# headstage.net
KiCad netlist of a schematic drawn in EAGLE
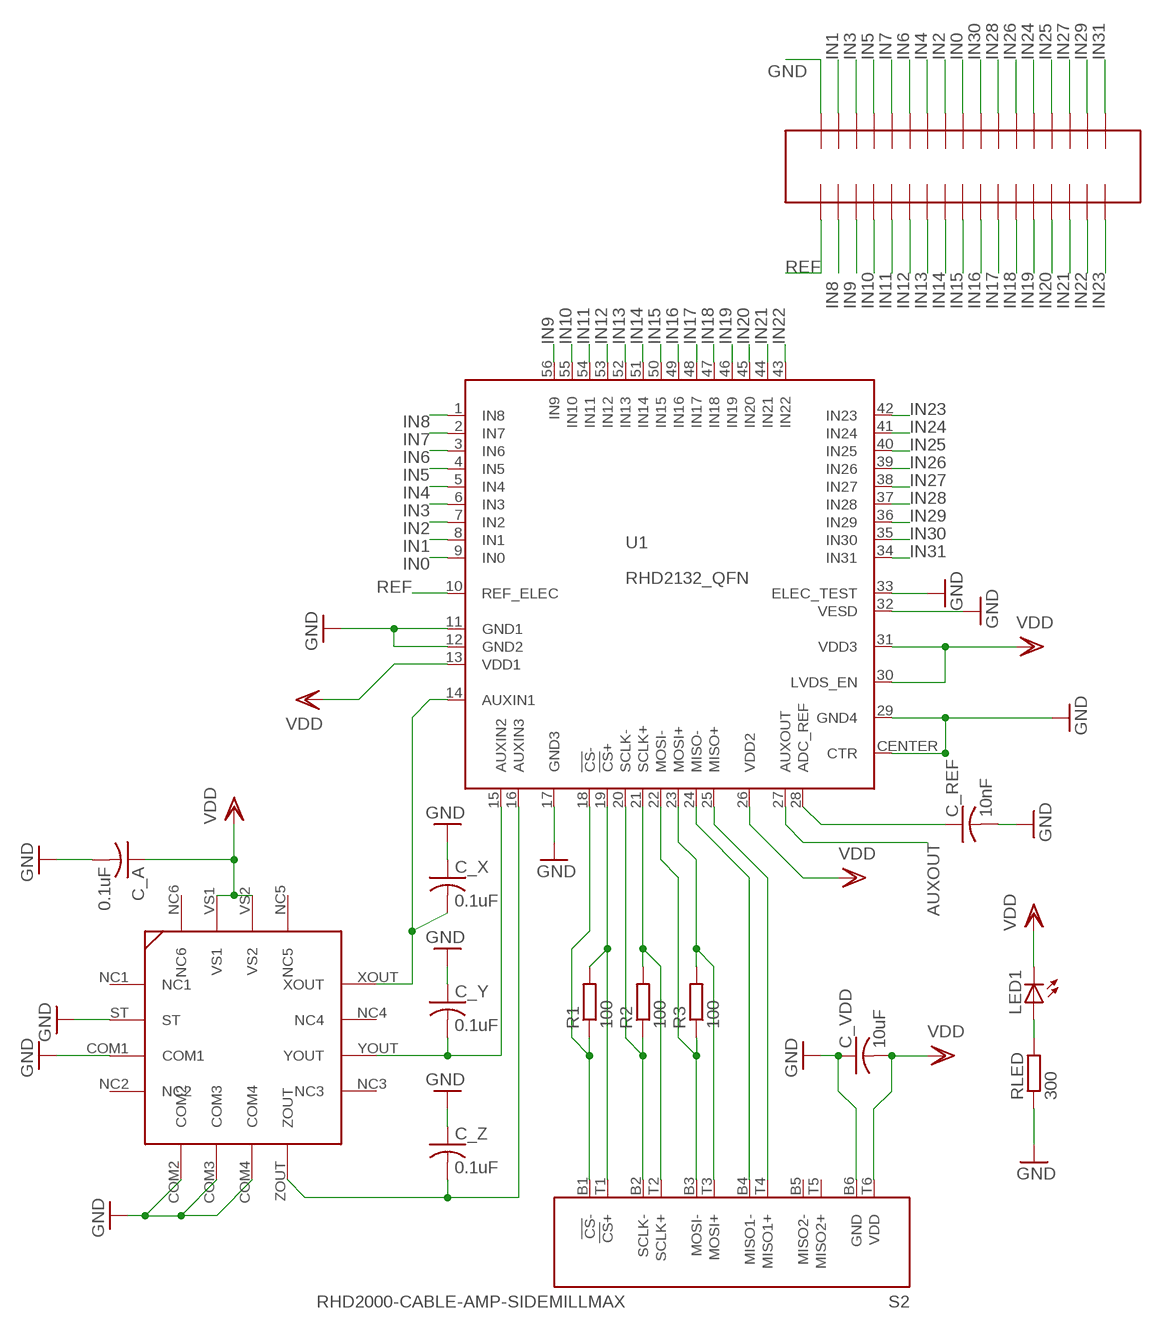
[diagram p0: schematic, sheet 1]

(export (version "E")
  (design (tool "Eeschema 10.0.6"))
  (components
    (comp (ref "C_A")
      (value "0.1uF")
      (footprint "eagle-import:C0402K")
      (libsource (lib "eagle-import") (part "resistor_C-USC0402K"))
    )
    (comp (ref "C_REF")
      (value "10nF")
      (footprint "eagle-import:C0402K")
      (libsource (lib "eagle-import") (part "resistor_C-USC0402K"))
    )
    (comp (ref "C_VDD")
      (value "10uF")
      (footprint "eagle-import:C0805")
      (libsource (lib "eagle-import") (part "C-USC0805"))
    )
    (comp (ref "C_X")
      (value "0.1uF")
      (footprint "eagle-import:C0402K")
      (libsource (lib "eagle-import") (part "resistor_C-USC0402K"))
    )
    (comp (ref "C_Y")
      (value "0.1uF")
      (footprint "eagle-import:C0402K")
      (libsource (lib "eagle-import") (part "resistor_C-USC0402K"))
    )
    (comp (ref "C_Z")
      (value "0.1uF")
      (footprint "eagle-import:C0402K")
      (libsource (lib "eagle-import") (part "resistor_C-USC0402K"))
    )
    (comp (ref "LED1")
      (value "LEDCHIPLED_0805")
      (footprint "eagle-import:CHIPLED_0805")
      (libsource (lib "eagle-import") (part "LEDCHIPLED_0805"))
    )
    (comp (ref "R1")
      (value "100")
      (footprint "eagle-import:R0402")
      (libsource (lib "eagle-import") (part "R-EU_R0402"))
    )
    (comp (ref "R2")
      (value "100")
      (footprint "eagle-import:R0402")
      (libsource (lib "eagle-import") (part "R-EU_R0402"))
    )
    (comp (ref "R3")
      (value "100")
      (footprint "eagle-import:R0402")
      (libsource (lib "eagle-import") (part "R-EU_R0402"))
    )
    (comp (ref "RLED")
      (value "300")
      (footprint "eagle-import:R0402")
      (libsource (lib "eagle-import") (part "R-EU_R0402"))
    )
    (comp (ref "S2")
      (value "RHD2000-CABLE-AMP-SIDEMILLMAX")
      (footprint "eagle-import:MILLMAX-12PIN")
      (libsource (lib "eagle-import") (part "RHD2000-CABLE-AMP-SIDEMILLMAX"))
    )
    (comp (ref "U$1")
      (value "ADXL335")
      (footprint "eagle-import:ADXL335")
      (libsource (lib "eagle-import") (part "ADXL335"))
    )
    (comp (ref "U$2")
      (value "FTSH-117BOARD-END")
      (footprint "eagle-import:FTSH-117-END")
      (libsource (lib "eagle-import") (part "FTSH-117BOARD-END"))
    )
    (comp (ref "U1")
      (value "RHD2132_QFN")
      (footprint "eagle-import:QFN56_8_X_8_LARGE")
      (libsource (lib "eagle-import") (part "RHD2132_QFN"))
    )
  )
  (nets
    (net (code "1") (name "/AUXOUT") (class "Default")
      (node (ref "U1") (pin "27") (pinfunction "AUXOUT_27") (pintype "tri_state"))
    )
    (net (code "2") (name "/IN0") (class "Default")
      (node (ref "U$2") (pin "P$26") (pinfunction "P$26_P$26") (pintype "bidirectional"))
      (node (ref "U1") (pin "9") (pinfunction "IN0_9") (pintype "input"))
    )
    (net (code "3") (name "/IN1") (class "Default")
      (node (ref "U$2") (pin "P$33") (pinfunction "P$33_P$33") (pintype "bidirectional"))
      (node (ref "U1") (pin "8") (pinfunction "IN1_8") (pintype "input"))
    )
    (net (code "4") (name "/IN2") (class "Default")
      (node (ref "U$2") (pin "P$27") (pinfunction "P$27_P$27") (pintype "bidirectional"))
      (node (ref "U1") (pin "7") (pinfunction "IN2_7") (pintype "input"))
    )
    (net (code "5") (name "/IN3") (class "Default")
      (node (ref "U$2") (pin "P$32") (pinfunction "P$32_P$32") (pintype "bidirectional"))
      (node (ref "U1") (pin "6") (pinfunction "IN3_6") (pintype "input"))
    )
    (net (code "6") (name "/IN4") (class "Default")
      (node (ref "U$2") (pin "P$28") (pinfunction "P$28_P$28") (pintype "bidirectional"))
      (node (ref "U1") (pin "5") (pinfunction "IN4_5") (pintype "input"))
    )
    (net (code "7") (name "/IN5") (class "Default")
      (node (ref "U$2") (pin "P$31") (pinfunction "P$31_P$31") (pintype "bidirectional"))
      (node (ref "U1") (pin "4") (pinfunction "IN5_4") (pintype "input"))
    )
    (net (code "8") (name "/IN6") (class "Default")
      (node (ref "U$2") (pin "P$29") (pinfunction "P$29_P$29") (pintype "bidirectional"))
      (node (ref "U1") (pin "3") (pinfunction "IN6_3") (pintype "input"))
    )
    (net (code "9") (name "/IN7") (class "Default")
      (node (ref "U$2") (pin "P$30") (pinfunction "P$30_P$30") (pintype "bidirectional"))
      (node (ref "U1") (pin "2") (pinfunction "IN7_2") (pintype "input"))
    )
    (net (code "10") (name "/IN8") (class "Default")
      (node (ref "U$2") (pin "P$2") (pinfunction "P$2_P$2") (pintype "bidirectional"))
      (node (ref "U1") (pin "1") (pinfunction "IN8_1") (pintype "input"))
    )
    (net (code "11") (name "/IN9") (class "Default")
      (node (ref "U$2") (pin "P$3") (pinfunction "P$3_P$3") (pintype "bidirectional"))
      (node (ref "U1") (pin "56") (pinfunction "IN9_56") (pintype "input"))
    )
    (net (code "12") (name "/IN10") (class "Default")
      (node (ref "U$2") (pin "P$4") (pinfunction "P$4_P$4") (pintype "bidirectional"))
      (node (ref "U1") (pin "55") (pinfunction "IN10_55") (pintype "input"))
    )
    (net (code "13") (name "/IN11") (class "Default")
      (node (ref "U$2") (pin "P$5") (pinfunction "P$5_P$5") (pintype "bidirectional"))
      (node (ref "U1") (pin "54") (pinfunction "IN11_54") (pintype "input"))
    )
    (net (code "14") (name "/IN12") (class "Default")
      (node (ref "U$2") (pin "P$6") (pinfunction "P$6_P$6") (pintype "bidirectional"))
      (node (ref "U1") (pin "53") (pinfunction "IN12_53") (pintype "input"))
    )
    (net (code "15") (name "/IN13") (class "Default")
      (node (ref "U$2") (pin "P$7") (pinfunction "P$7_P$7") (pintype "bidirectional"))
      (node (ref "U1") (pin "52") (pinfunction "IN13_52") (pintype "input"))
    )
    (net (code "16") (name "/IN14") (class "Default")
      (node (ref "U$2") (pin "P$8") (pinfunction "P$8_P$8") (pintype "bidirectional"))
      (node (ref "U1") (pin "51") (pinfunction "IN14_51") (pintype "input"))
    )
    (net (code "17") (name "/IN15") (class "Default")
      (node (ref "U$2") (pin "P$9") (pinfunction "P$9_P$9") (pintype "bidirectional"))
      (node (ref "U1") (pin "50") (pinfunction "IN15_50") (pintype "input"))
    )
    (net (code "18") (name "/IN16") (class "Default")
      (node (ref "U$2") (pin "P$10") (pinfunction "P$10_P$10") (pintype "bidirectional"))
      (node (ref "U1") (pin "49") (pinfunction "IN16_49") (pintype "input"))
    )
    (net (code "19") (name "/IN17") (class "Default")
      (node (ref "U$2") (pin "P$11") (pinfunction "P$11_P$11") (pintype "bidirectional"))
      (node (ref "U1") (pin "48") (pinfunction "IN17_48") (pintype "input"))
    )
    (net (code "20") (name "/IN18") (class "Default")
      (node (ref "U$2") (pin "P$12") (pinfunction "P$12_P$12") (pintype "bidirectional"))
      (node (ref "U1") (pin "47") (pinfunction "IN18_47") (pintype "input"))
    )
    (net (code "21") (name "/IN19") (class "Default")
      (node (ref "U$2") (pin "P$13") (pinfunction "P$13_P$13") (pintype "bidirectional"))
      (node (ref "U1") (pin "46") (pinfunction "IN19_46") (pintype "input"))
    )
    (net (code "22") (name "/IN20") (class "Default")
      (node (ref "U$2") (pin "P$14") (pinfunction "P$14_P$14") (pintype "bidirectional"))
      (node (ref "U1") (pin "45") (pinfunction "IN20_45") (pintype "input"))
    )
    (net (code "23") (name "/IN21") (class "Default")
      (node (ref "U$2") (pin "P$15") (pinfunction "P$15_P$15") (pintype "bidirectional"))
      (node (ref "U1") (pin "44") (pinfunction "IN21_44") (pintype "input"))
    )
    (net (code "24") (name "/IN22") (class "Default")
      (node (ref "U$2") (pin "P$16") (pinfunction "P$16_P$16") (pintype "bidirectional"))
      (node (ref "U1") (pin "43") (pinfunction "IN22_43") (pintype "input"))
    )
    (net (code "25") (name "/IN23") (class "Default")
      (node (ref "U$2") (pin "P$17") (pinfunction "P$17_P$17") (pintype "bidirectional"))
      (node (ref "U1") (pin "42") (pinfunction "IN23_42") (pintype "input"))
    )
    (net (code "26") (name "/IN24") (class "Default")
      (node (ref "U$2") (pin "P$22") (pinfunction "P$22_P$22") (pintype "bidirectional"))
      (node (ref "U1") (pin "41") (pinfunction "IN24_41") (pintype "input"))
    )
    (net (code "27") (name "/IN25") (class "Default")
      (node (ref "U$2") (pin "P$21") (pinfunction "P$21_P$21") (pintype "bidirectional"))
      (node (ref "U1") (pin "40") (pinfunction "IN25_40") (pintype "input"))
    )
    (net (code "28") (name "/IN26") (class "Default")
      (node (ref "U$2") (pin "P$23") (pinfunction "P$23_P$23") (pintype "bidirectional"))
      (node (ref "U1") (pin "39") (pinfunction "IN26_39") (pintype "input"))
    )
    (net (code "29") (name "/IN27") (class "Default")
      (node (ref "U$2") (pin "P$20") (pinfunction "P$20_P$20") (pintype "bidirectional"))
      (node (ref "U1") (pin "38") (pinfunction "IN27_38") (pintype "input"))
    )
    (net (code "30") (name "/IN28") (class "Default")
      (node (ref "U$2") (pin "P$24") (pinfunction "P$24_P$24") (pintype "bidirectional"))
      (node (ref "U1") (pin "37") (pinfunction "IN28_37") (pintype "input"))
    )
    (net (code "31") (name "/IN29") (class "Default")
      (node (ref "U$2") (pin "P$19") (pinfunction "P$19_P$19") (pintype "bidirectional"))
      (node (ref "U1") (pin "36") (pinfunction "IN29_36") (pintype "input"))
    )
    (net (code "32") (name "/IN30") (class "Default")
      (node (ref "U$2") (pin "P$25") (pinfunction "P$25_P$25") (pintype "bidirectional"))
      (node (ref "U1") (pin "35") (pinfunction "IN30_35") (pintype "input"))
    )
    (net (code "33") (name "/IN31") (class "Default")
      (node (ref "U$2") (pin "P$18") (pinfunction "P$18_P$18") (pintype "bidirectional"))
      (node (ref "U1") (pin "34") (pinfunction "IN31_34") (pintype "input"))
    )
    (net (code "34") (name "/REF") (class "Default")
      (node (ref "U$2") (pin "P$1") (pinfunction "P$1_P$1") (pintype "bidirectional"))
      (node (ref "U1") (pin "10") (pinfunction "REF_ELEC_10") (pintype "input"))
    )
    (net (code "35") (name "GND") (class "Default")
      (node (ref "C_A") (pin "2") (pinfunction "2_2") (pintype "passive"))
      (node (ref "C_REF") (pin "2") (pinfunction "2_2") (pintype "passive"))
      (node (ref "C_VDD") (pin "1") (pinfunction "1_1") (pintype "passive"))
      (node (ref "C_X") (pin "1") (pinfunction "1_1") (pintype "passive"))
      (node (ref "C_Y") (pin "1") (pinfunction "1_1") (pintype "passive"))
      (node (ref "C_Z") (pin "1") (pinfunction "1_1") (pintype "passive"))
      (node (ref "RLED") (pin "1") (pinfunction "1_1") (pintype "passive"))
      (node (ref "S2") (pin "B6") (pinfunction "GND_B6") (pintype "power_in"))
      (node (ref "U$1") (pin "COM1") (pinfunction "COM1_COM1") (pintype "bidirectional"))
      (node (ref "U$1") (pin "COM2") (pinfunction "COM2_COM2") (pintype "bidirectional"))
      (node (ref "U$1") (pin "COM3") (pinfunction "COM3_COM3") (pintype "bidirectional"))
      (node (ref "U$1") (pin "COM4") (pinfunction "COM4_COM4") (pintype "bidirectional"))
      (node (ref "U$1") (pin "ST") (pinfunction "ST_ST") (pintype "bidirectional"))
      (node (ref "U$2") (pin "P$34") (pinfunction "P$34_P$34") (pintype "bidirectional"))
      (node (ref "U1") (pin "11") (pinfunction "GND1_11") (pintype "power_in"))
      (node (ref "U1") (pin "12") (pinfunction "GND2_12") (pintype "power_in"))
      (node (ref "U1") (pin "17") (pinfunction "GND3_17") (pintype "power_in"))
      (node (ref "U1") (pin "29") (pinfunction "GND4_29") (pintype "power_in"))
      (node (ref "U1") (pin "32") (pinfunction "VESD_32") (pintype "power_in"))
      (node (ref "U1") (pin "33") (pinfunction "ELEC_TEST_33") (pintype "input"))
      (node (ref "U1") (pin "CENTER") (pinfunction "CTR_CENTER") (pintype "power_in"))
    )
    (net (code "36") (name "Net-(LED1-PadA)") (class "Default")
      (node (ref "LED1") (pin "A") (pinfunction "A_A") (pintype "passive"))
      (node (ref "RLED") (pin "2") (pinfunction "2_2") (pintype "passive"))
    )
    (net (code "37") (name "Net-(S2-MISO1+)") (class "Default")
      (node (ref "S2") (pin "T4") (pinfunction "MISO1+_T4") (pintype "bidirectional"))
      (node (ref "U1") (pin "25") (pinfunction "MISO+_25") (pintype "output"))
    )
    (net (code "38") (name "Net-(S2-MISO1-)") (class "Default")
      (node (ref "S2") (pin "B4") (pinfunction "MISO1-_B4") (pintype "bidirectional"))
      (node (ref "U1") (pin "24") (pinfunction "MISO-_24") (pintype "output"))
    )
    (net (code "39") (name "Net-(S2-MOSI+)") (class "Default")
      (node (ref "R3") (pin "2") (pinfunction "2_2") (pintype "passive"))
      (node (ref "S2") (pin "T3") (pinfunction "MOSI+_T3") (pintype "bidirectional"))
      (node (ref "U1") (pin "23") (pinfunction "MOSI+_23") (pintype "input"))
    )
    (net (code "40") (name "Net-(S2-MOSI-)") (class "Default")
      (node (ref "R3") (pin "1") (pinfunction "1_1") (pintype "passive"))
      (node (ref "S2") (pin "B3") (pinfunction "MOSI-_B3") (pintype "bidirectional"))
      (node (ref "U1") (pin "22") (pinfunction "MOSI-_22") (pintype "input"))
    )
    (net (code "41") (name "Net-(S2-SCLK+)") (class "Default")
      (node (ref "R2") (pin "2") (pinfunction "2_2") (pintype "passive"))
      (node (ref "S2") (pin "T2") (pinfunction "SCLK+_T2") (pintype "bidirectional"))
      (node (ref "U1") (pin "21") (pinfunction "SCLK+_21") (pintype "input"))
    )
    (net (code "42") (name "Net-(S2-SCLK-)") (class "Default")
      (node (ref "R2") (pin "1") (pinfunction "1_1") (pintype "passive"))
      (node (ref "S2") (pin "B2") (pinfunction "SCLK-_B2") (pintype "bidirectional"))
      (node (ref "U1") (pin "20") (pinfunction "SCLK-_20") (pintype "input"))
    )
    (net (code "43") (name "Net-(S2-~{CS}+)") (class "Default")
      (node (ref "R1") (pin "2") (pinfunction "2_2") (pintype "passive"))
      (node (ref "S2") (pin "T1") (pinfunction "~{CS}+_T1") (pintype "bidirectional"))
      (node (ref "U1") (pin "19") (pinfunction "~{CS}+_19") (pintype "input"))
    )
    (net (code "44") (name "Net-(S2-~{CS}-)") (class "Default")
      (node (ref "R1") (pin "1") (pinfunction "1_1") (pintype "passive"))
      (node (ref "S2") (pin "B1") (pinfunction "~{CS}-_B1") (pintype "bidirectional"))
      (node (ref "U1") (pin "18") (pinfunction "~{CS}-_18") (pintype "input"))
    )
    (net (code "45") (name "Net-(U1-ADC_REF)") (class "Default")
      (node (ref "C_REF") (pin "1") (pinfunction "1_1") (pintype "passive"))
      (node (ref "U1") (pin "28") (pinfunction "ADC_REF_28") (pintype "passive"))
    )
    (net (code "46") (name "Net-(U1-AUXIN1)") (class "Default")
      (node (ref "C_X") (pin "2") (pinfunction "2_2") (pintype "passive"))
      (node (ref "U$1") (pin "XOUT") (pinfunction "XOUT_XOUT") (pintype "bidirectional"))
      (node (ref "U1") (pin "14") (pinfunction "AUXIN1_14") (pintype "input"))
    )
    (net (code "47") (name "Net-(U1-AUXIN2)") (class "Default")
      (node (ref "C_Y") (pin "2") (pinfunction "2_2") (pintype "passive"))
      (node (ref "U$1") (pin "YOUT") (pinfunction "YOUT_YOUT") (pintype "bidirectional"))
      (node (ref "U1") (pin "15") (pinfunction "AUXIN2_15") (pintype "input"))
    )
    (net (code "48") (name "Net-(U1-AUXIN3)") (class "Default")
      (node (ref "C_Z") (pin "2") (pinfunction "2_2") (pintype "passive"))
      (node (ref "U$1") (pin "ZOUT") (pinfunction "ZOUT_ZOUT") (pintype "bidirectional"))
      (node (ref "U1") (pin "16") (pinfunction "AUXIN3_16") (pintype "input"))
    )
    (net (code "49") (name "VDD") (class "Default")
      (node (ref "C_A") (pin "1") (pinfunction "1_1") (pintype "passive"))
      (node (ref "C_VDD") (pin "2") (pinfunction "2_2") (pintype "passive"))
      (node (ref "LED1") (pin "C") (pinfunction "C_C") (pintype "passive"))
      (node (ref "S2") (pin "T6") (pinfunction "VDD_T6") (pintype "bidirectional"))
      (node (ref "U$1") (pin "VS1") (pinfunction "VS1_VS1") (pintype "bidirectional"))
      (node (ref "U$1") (pin "VS2") (pinfunction "VS2_VS2") (pintype "bidirectional"))
      (node (ref "U1") (pin "13") (pinfunction "VDD1_13") (pintype "power_in"))
      (node (ref "U1") (pin "26") (pinfunction "VDD2_26") (pintype "power_in"))
      (node (ref "U1") (pin "30") (pinfunction "LVDS_EN_30") (pintype "input"))
      (node (ref "U1") (pin "31") (pinfunction "VDD3_31") (pintype "power_in"))
    )
    (net (code "50") (name "unconnected-(S2-MISO2+-PadT5)") (class "Default")
      (node (ref "S2") (pin "T5") (pinfunction "MISO2+_T5") (pintype "bidirectional"))
    )
    (net (code "51") (name "unconnected-(S2-MISO2--PadB5)") (class "Default")
      (node (ref "S2") (pin "B5") (pinfunction "MISO2-_B5") (pintype "bidirectional"))
    )
    (net (code "52") (name "unconnected-(U$1-PadNC1)") (class "Default")
      (node (ref "U$1") (pin "NC1") (pinfunction "NC1_NC1") (pintype "bidirectional"))
    )
    (net (code "53") (name "unconnected-(U$1-PadNC2)") (class "Default")
      (node (ref "U$1") (pin "NC2") (pinfunction "NC2_NC2") (pintype "bidirectional"))
    )
    (net (code "54") (name "unconnected-(U$1-PadNC3)") (class "Default")
      (node (ref "U$1") (pin "NC3") (pinfunction "NC3_NC3") (pintype "bidirectional"))
    )
    (net (code "55") (name "unconnected-(U$1-PadNC4)") (class "Default")
      (node (ref "U$1") (pin "NC4") (pinfunction "NC4_NC4") (pintype "bidirectional"))
    )
    (net (code "56") (name "unconnected-(U$1-PadNC5)") (class "Default")
      (node (ref "U$1") (pin "NC5") (pinfunction "NC5_NC5") (pintype "bidirectional"))
    )
    (net (code "57") (name "unconnected-(U$1-PadNC6)") (class "Default")
      (node (ref "U$1") (pin "NC6") (pinfunction "NC6_NC6") (pintype "bidirectional"))
    )
  )
)
